# Ngu-nghiep.net
KiCad netlist of a schematic drawn in Altium Designer
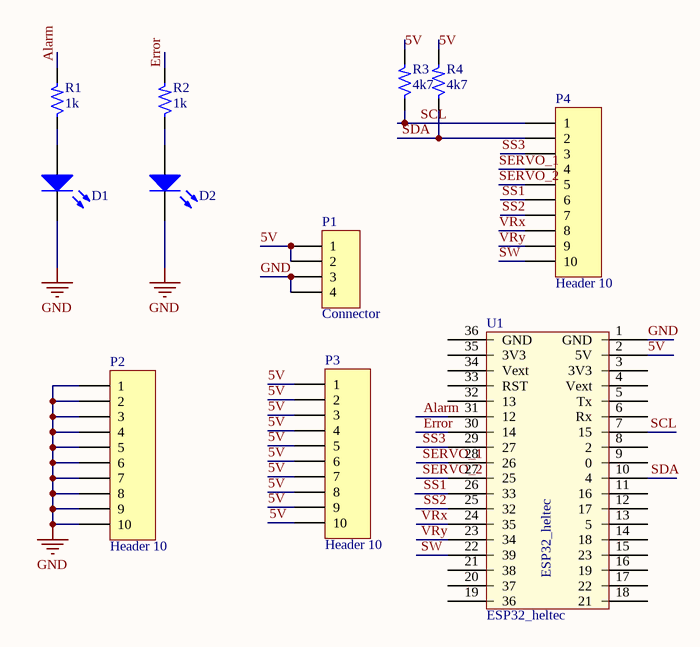
[diagram p0: Ngu-nghiep.schdoc]

(export (version "E")
  (design (tool "Eeschema 10.0.6"))
  (components
    (comp (ref "D1")
      (value "LED")
      (footprint "MinhTien_PcbLib:LED_3mm")
      (description "Typical INFRARED GaAs LED")
      (fields (field (name "PUBLISHER") "Altium Limited"))
      (libsource (lib "MinhTien_SCHLib") (part "LED"))
    )
    (comp (ref "D2")
      (value "LED")
      (footprint "MinhTien_PcbLib:LED_3mm")
      (description "Typical INFRARED GaAs LED")
      (fields (field (name "PUBLISHER") "Altium Limited"))
      (libsource (lib "MinhTien_SCHLib") (part "LED"))
    )
    (comp (ref "P1")
      (value "Connector")
      (footprint "MinhTien_PCBLib:JST-XH_B4B-XH-A")
      (libsource (lib "MinhTien_SCHLib") (part "Connector_4pin"))
    )
    (comp (ref "P2")
      (value "Header 10")
      (footprint "HDR1X10")
      (description "Header, 10-Pin")
      (fields (field (name "PUBLISHER") "Altium Limited"))
      (libsource (lib "My Library") (part "Header 10"))
    )
    (comp (ref "P3")
      (value "Header 10")
      (footprint "HDR1X10")
      (description "Header, 10-Pin")
      (fields (field (name "PUBLISHER") "Altium Limited"))
      (libsource (lib "My Library") (part "Header 10"))
    )
    (comp (ref "P4")
      (value "Header 10")
      (footprint "HDR1X10")
      (description "Header, 10-Pin")
      (fields (field (name "PUBLISHER") "Altium Limited"))
      (libsource (lib "My Library") (part "Header 10"))
    )
    (comp (ref "R1")
      (value "1k")
      (footprint "R1/8W")
      (description "Resistor 1/4W")
      (libsource (lib "My Library") (part "R"))
    )
    (comp (ref "R2")
      (value "1k")
      (footprint "R1/8W")
      (description "Resistor 1/4W")
      (libsource (lib "My Library") (part "R"))
    )
    (comp (ref "R3")
      (value "4k7")
      (footprint "R1/8W")
      (description "Resistor 1/4W")
      (libsource (lib "My Library") (part "R"))
    )
    (comp (ref "R4")
      (value "4k7")
      (footprint "R1/8W")
      (description "Resistor 1/4W")
      (libsource (lib "My Library") (part "R"))
    )
    (comp (ref "U1")
      (value "ESP32_heltec")
      (footprint "ESP32_WFK_Heltec")
      (description "ESP32 IOT kit")
      (libsource (lib "MinhTien_SCHLib") (part "ESP32_heltec"))
    )
  )
  (nets
    (net (code "1") (name "/5V") (class "Default")
      (node (ref "P1") (pin "1") (pinfunction "1_1") (pintype "passive"))
      (node (ref "P1") (pin "2") (pinfunction "2_2") (pintype "passive"))
      (node (ref "P3") (pin "1") (pinfunction "1_1") (pintype "passive"))
      (node (ref "P3") (pin "10") (pinfunction "10_10") (pintype "passive"))
      (node (ref "P3") (pin "2") (pinfunction "2_2") (pintype "passive"))
      (node (ref "P3") (pin "3") (pinfunction "3_3") (pintype "passive"))
      (node (ref "P3") (pin "4") (pinfunction "4_4") (pintype "passive"))
      (node (ref "P3") (pin "5") (pinfunction "5_5") (pintype "passive"))
      (node (ref "P3") (pin "6") (pinfunction "6_6") (pintype "passive"))
      (node (ref "P3") (pin "7") (pinfunction "7_7") (pintype "passive"))
      (node (ref "P3") (pin "8") (pinfunction "8_8") (pintype "passive"))
      (node (ref "P3") (pin "9") (pinfunction "9_9") (pintype "passive"))
      (node (ref "R3") (pin "2") (pinfunction "2_2") (pintype "passive"))
      (node (ref "R4") (pin "2") (pinfunction "2_2") (pintype "passive"))
      (node (ref "U1") (pin "2") (pinfunction "5V_2") (pintype "passive"))
    )
    (net (code "2") (name "/Alarm") (class "Default")
      (node (ref "R1") (pin "2") (pinfunction "2_2") (pintype "passive"))
      (node (ref "U1") (pin "31") (pinfunction "12_31") (pintype "passive"))
    )
    (net (code "3") (name "/Error") (class "Default")
      (node (ref "R2") (pin "2") (pinfunction "2_2") (pintype "passive"))
      (node (ref "U1") (pin "30") (pinfunction "14_30") (pintype "passive"))
    )
    (net (code "4") (name "/SCL") (class "Default")
      (node (ref "P4") (pin "1") (pinfunction "1_1") (pintype "passive"))
      (node (ref "R3") (pin "1") (pinfunction "1_1") (pintype "passive"))
      (node (ref "U1") (pin "7") (pinfunction "15_7") (pintype "passive"))
    )
    (net (code "5") (name "/SDA") (class "Default")
      (node (ref "P4") (pin "2") (pinfunction "2_2") (pintype "passive"))
      (node (ref "R4") (pin "1") (pinfunction "1_1") (pintype "passive"))
      (node (ref "U1") (pin "10") (pinfunction "4_10") (pintype "passive"))
    )
    (net (code "6") (name "/SERVO_1") (class "Default")
      (node (ref "P4") (pin "4") (pinfunction "4_4") (pintype "passive"))
      (node (ref "U1") (pin "28") (pinfunction "26_28") (pintype "passive"))
    )
    (net (code "7") (name "/SERVO_2") (class "Default")
      (node (ref "P4") (pin "5") (pinfunction "5_5") (pintype "passive"))
      (node (ref "U1") (pin "27") (pinfunction "25_27") (pintype "passive"))
    )
    (net (code "8") (name "/SS1") (class "Default")
      (node (ref "P4") (pin "6") (pinfunction "6_6") (pintype "passive"))
      (node (ref "U1") (pin "26") (pinfunction "33_26") (pintype "passive"))
    )
    (net (code "9") (name "/SS2") (class "Default")
      (node (ref "P4") (pin "7") (pinfunction "7_7") (pintype "passive"))
      (node (ref "U1") (pin "25") (pinfunction "32_25") (pintype "passive"))
    )
    (net (code "10") (name "/SS3") (class "Default")
      (node (ref "P4") (pin "3") (pinfunction "3_3") (pintype "passive"))
      (node (ref "U1") (pin "29") (pinfunction "27_29") (pintype "passive"))
    )
    (net (code "11") (name "/SW") (class "Default")
      (node (ref "P4") (pin "10") (pinfunction "10_10") (pintype "passive"))
      (node (ref "U1") (pin "22") (pinfunction "39_22") (pintype "passive"))
    )
    (net (code "12") (name "/VRx") (class "Default")
      (node (ref "P4") (pin "8") (pinfunction "8_8") (pintype "passive"))
      (node (ref "U1") (pin "24") (pinfunction "35_24") (pintype "passive"))
    )
    (net (code "13") (name "/VRy") (class "Default")
      (node (ref "P4") (pin "9") (pinfunction "9_9") (pintype "passive"))
      (node (ref "U1") (pin "23") (pinfunction "34_23") (pintype "passive"))
    )
    (net (code "14") (name "GND") (class "Default")
      (node (ref "D1") (pin "2") (pinfunction "K_2") (pintype "passive"))
      (node (ref "D2") (pin "2") (pinfunction "K_2") (pintype "passive"))
      (node (ref "P1") (pin "3") (pinfunction "3_3") (pintype "passive"))
      (node (ref "P1") (pin "4") (pinfunction "4_4") (pintype "passive"))
      (node (ref "P2") (pin "1") (pinfunction "1_1") (pintype "passive"))
      (node (ref "P2") (pin "10") (pinfunction "10_10") (pintype "passive"))
      (node (ref "P2") (pin "2") (pinfunction "2_2") (pintype "passive"))
      (node (ref "P2") (pin "3") (pinfunction "3_3") (pintype "passive"))
      (node (ref "P2") (pin "4") (pinfunction "4_4") (pintype "passive"))
      (node (ref "P2") (pin "5") (pinfunction "5_5") (pintype "passive"))
      (node (ref "P2") (pin "6") (pinfunction "6_6") (pintype "passive"))
      (node (ref "P2") (pin "7") (pinfunction "7_7") (pintype "passive"))
      (node (ref "P2") (pin "8") (pinfunction "8_8") (pintype "passive"))
      (node (ref "P2") (pin "9") (pinfunction "9_9") (pintype "passive"))
      (node (ref "U1") (pin "1") (pinfunction "GND_1") (pintype "passive"))
    )
    (net (code "15") (name "Net-(D1-A)") (class "Default")
      (node (ref "D1") (pin "1") (pinfunction "A_1") (pintype "passive"))
      (node (ref "R1") (pin "1") (pinfunction "1_1") (pintype "passive"))
    )
    (net (code "16") (name "Net-(D2-A)") (class "Default")
      (node (ref "D2") (pin "1") (pinfunction "A_1") (pintype "passive"))
      (node (ref "R2") (pin "1") (pinfunction "1_1") (pintype "passive"))
    )
    (net (code "17") (name "unconnected-(U1-0-Pad9)") (class "Default")
      (node (ref "U1") (pin "9") (pinfunction "0_9") (pintype "passive"))
    )
    (net (code "18") (name "unconnected-(U1-2-Pad8)") (class "Default")
      (node (ref "U1") (pin "8") (pinfunction "2_8") (pintype "passive"))
    )
    (net (code "19") (name "unconnected-(U1-3V3-Pad3)") (class "Default")
      (node (ref "U1") (pin "3") (pinfunction "3V3_3") (pintype "passive"))
    )
    (net (code "20") (name "unconnected-(U1-3V3-Pad35)") (class "Default")
      (node (ref "U1") (pin "35") (pinfunction "3V3_35") (pintype "passive"))
    )
    (net (code "21") (name "unconnected-(U1-5-Pad13)") (class "Default")
      (node (ref "U1") (pin "13") (pinfunction "5_13") (pintype "passive"))
    )
    (net (code "22") (name "unconnected-(U1-13-Pad32)") (class "Default")
      (node (ref "U1") (pin "32") (pinfunction "13_32") (pintype "passive"))
    )
    (net (code "23") (name "unconnected-(U1-16-Pad11)") (class "Default")
      (node (ref "U1") (pin "11") (pinfunction "16_11") (pintype "passive"))
    )
    (net (code "24") (name "unconnected-(U1-17-Pad12)") (class "Default")
      (node (ref "U1") (pin "12") (pinfunction "17_12") (pintype "passive"))
    )
    (net (code "25") (name "unconnected-(U1-18-Pad14)") (class "Default")
      (node (ref "U1") (pin "14") (pinfunction "18_14") (pintype "passive"))
    )
    (net (code "26") (name "unconnected-(U1-19-Pad16)") (class "Default")
      (node (ref "U1") (pin "16") (pinfunction "19_16") (pintype "passive"))
    )
    (net (code "27") (name "unconnected-(U1-21-Pad18)") (class "Default")
      (node (ref "U1") (pin "18") (pinfunction "21_18") (pintype "passive"))
    )
    (net (code "28") (name "unconnected-(U1-22-Pad17)") (class "Default")
      (node (ref "U1") (pin "17") (pinfunction "22_17") (pintype "passive"))
    )
    (net (code "29") (name "unconnected-(U1-23-Pad15)") (class "Default")
      (node (ref "U1") (pin "15") (pinfunction "23_15") (pintype "passive"))
    )
    (net (code "30") (name "unconnected-(U1-36-Pad19)") (class "Default")
      (node (ref "U1") (pin "19") (pinfunction "36_19") (pintype "passive"))
    )
    (net (code "31") (name "unconnected-(U1-37-Pad20)") (class "Default")
      (node (ref "U1") (pin "20") (pinfunction "37_20") (pintype "passive"))
    )
    (net (code "32") (name "unconnected-(U1-38-Pad21)") (class "Default")
      (node (ref "U1") (pin "21") (pinfunction "38_21") (pintype "passive"))
    )
    (net (code "33") (name "unconnected-(U1-GND-Pad36)") (class "Default")
      (node (ref "U1") (pin "36") (pinfunction "GND_36") (pintype "passive"))
    )
    (net (code "34") (name "unconnected-(U1-RST-Pad33)") (class "Default")
      (node (ref "U1") (pin "33") (pinfunction "RST_33") (pintype "passive"))
    )
    (net (code "35") (name "unconnected-(U1-Rx-Pad6)") (class "Default")
      (node (ref "U1") (pin "6") (pinfunction "Rx_6") (pintype "passive"))
    )
    (net (code "36") (name "unconnected-(U1-Tx-Pad5)") (class "Default")
      (node (ref "U1") (pin "5") (pinfunction "Tx_5") (pintype "passive"))
    )
    (net (code "37") (name "unconnected-(U1-Vext-Pad4)") (class "Default")
      (node (ref "U1") (pin "4") (pinfunction "Vext_4") (pintype "passive"))
    )
    (net (code "38") (name "unconnected-(U1-Vext-Pad34)") (class "Default")
      (node (ref "U1") (pin "34") (pinfunction "Vext_34") (pintype "passive"))
    )
  )
)
